# mppt.net
KiCad netlist of a schematic drawn in EAGLE
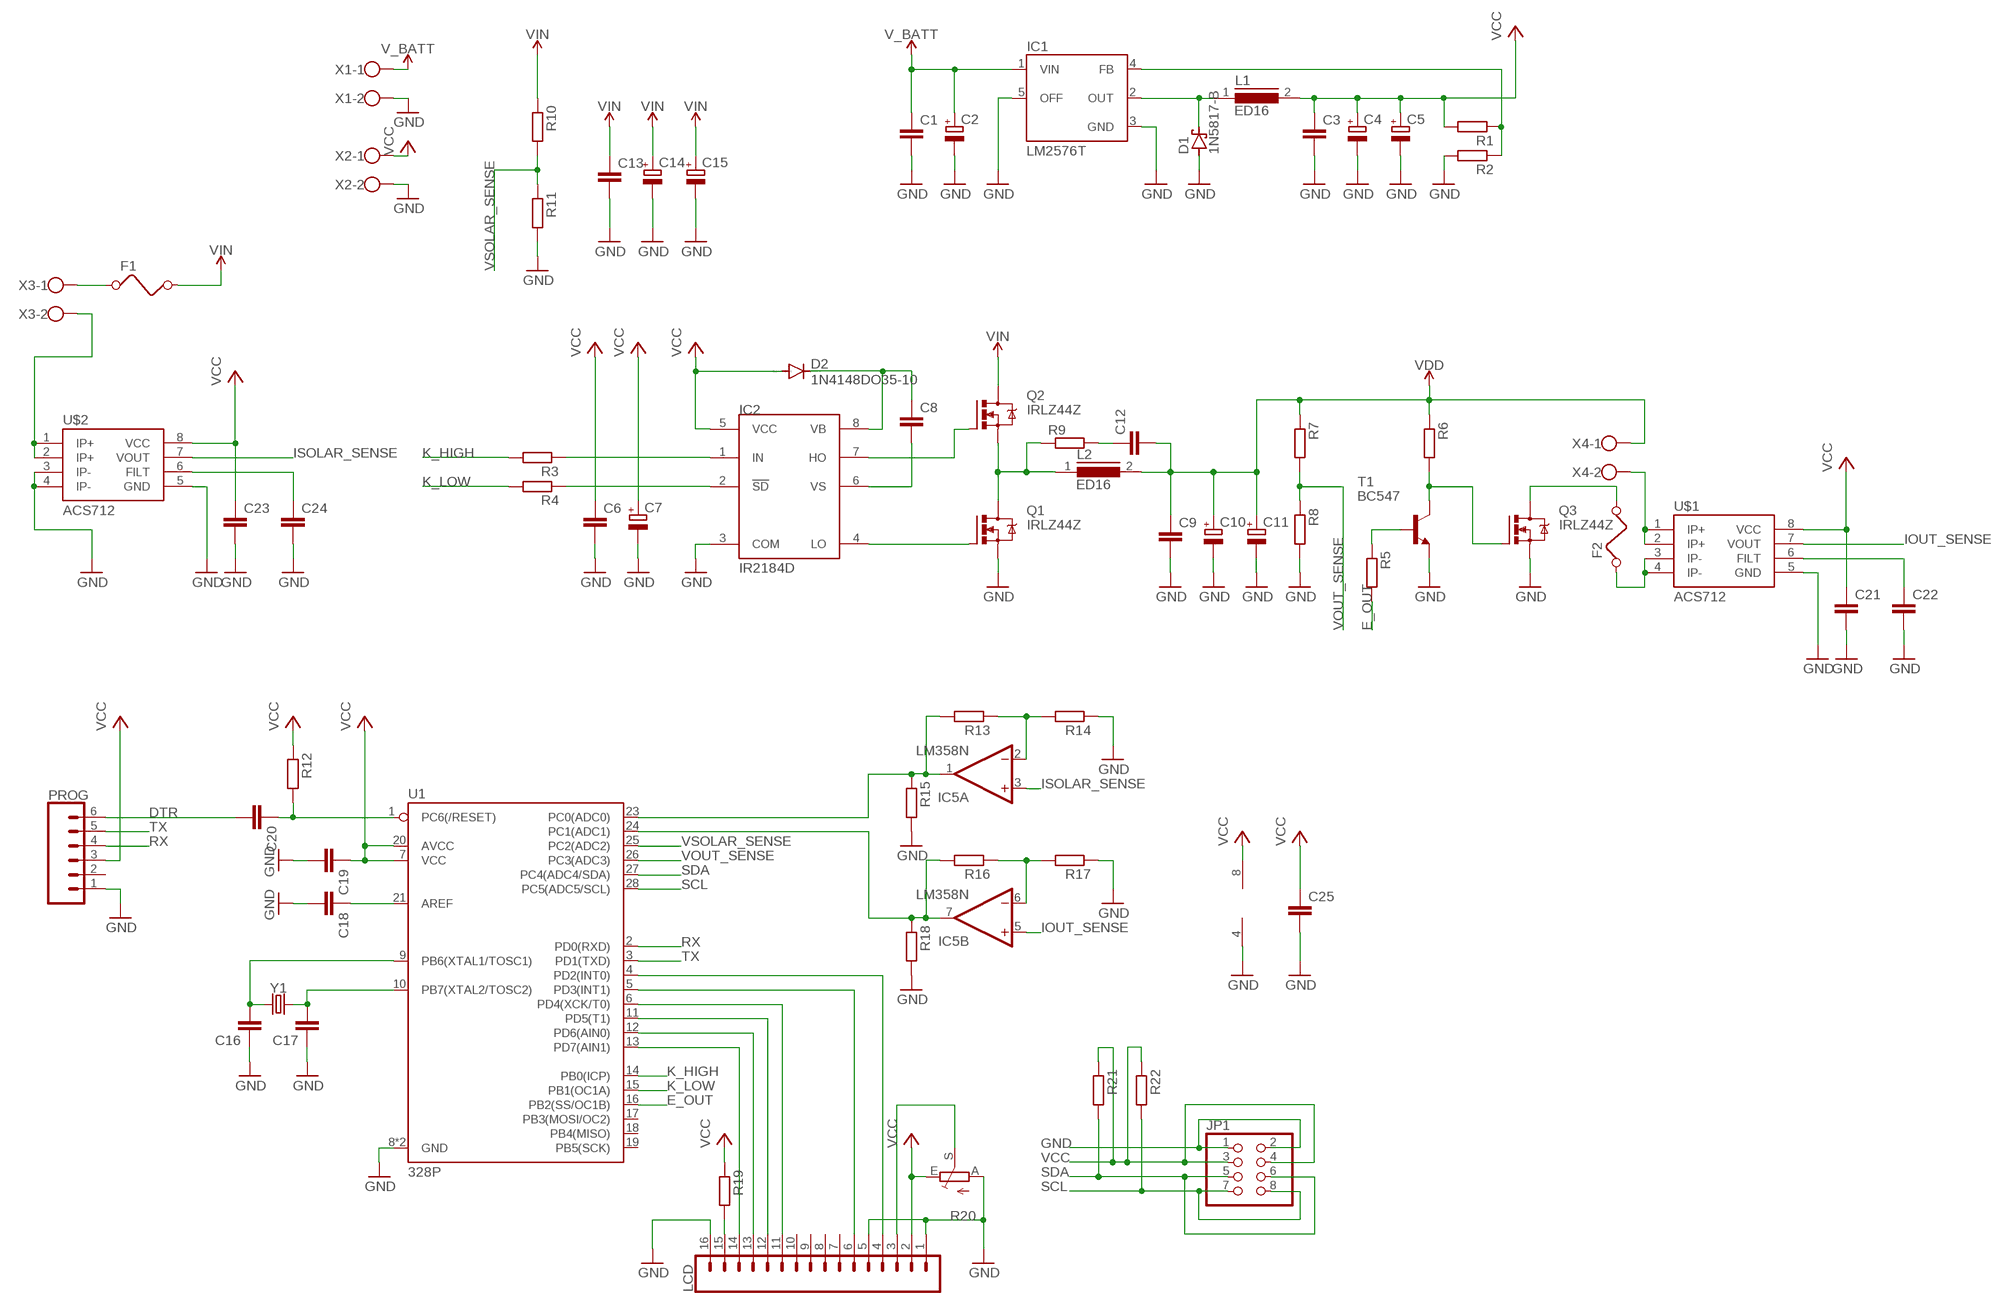
[diagram p0: schematic, sheet 1]

(export (version "E")
  (design (tool "Eeschema 10.0.6"))
  (components
    (comp (ref "C1")
      (value "C-EU025-024X044")
      (footprint "eagle-import:C025-024X044")
      (libsource (lib "eagle-import") (part "C-EU025-024X044"))
    )
    (comp (ref "C2")
      (value "CPOL-EUE5-6")
      (footprint "eagle-import:E5-6")
      (libsource (lib "eagle-import") (part "CPOL-EUE5-6"))
    )
    (comp (ref "C3")
      (value "C-EU025-024X044")
      (footprint "eagle-import:C025-024X044")
      (libsource (lib "eagle-import") (part "C-EU025-024X044"))
    )
    (comp (ref "C4")
      (value "CPOL-EUE5-6")
      (footprint "eagle-import:E5-6")
      (libsource (lib "eagle-import") (part "CPOL-EUE5-6"))
    )
    (comp (ref "C5")
      (value "CPOL-EUE5-6")
      (footprint "eagle-import:E5-6")
      (libsource (lib "eagle-import") (part "CPOL-EUE5-6"))
    )
    (comp (ref "C6")
      (value "C-EU025-024X044")
      (footprint "eagle-import:C025-024X044")
      (libsource (lib "eagle-import") (part "C-EU025-024X044"))
    )
    (comp (ref "C7")
      (value "CPOL-EUE5-6")
      (footprint "eagle-import:E5-6")
      (libsource (lib "eagle-import") (part "CPOL-EUE5-6"))
    )
    (comp (ref "C8")
      (value "C-EU025-024X044")
      (footprint "eagle-import:C025-024X044")
      (libsource (lib "eagle-import") (part "C-EU025-024X044"))
    )
    (comp (ref "C9")
      (value "C-EU025-024X044")
      (footprint "eagle-import:C025-024X044")
      (libsource (lib "eagle-import") (part "C-EU025-024X044"))
    )
    (comp (ref "C10")
      (value "CPOL-EUE7.5-16")
      (footprint "eagle-import:E7,5-16")
      (libsource (lib "eagle-import") (part "CPOL-EUE7.5-16"))
    )
    (comp (ref "C11")
      (value "CPOL-EUE7.5-16")
      (footprint "eagle-import:E7,5-16")
      (libsource (lib "eagle-import") (part "CPOL-EUE7.5-16"))
    )
    (comp (ref "C12")
      (value "C-EU025-024X044")
      (footprint "eagle-import:C025-024X044")
      (libsource (lib "eagle-import") (part "C-EU025-024X044"))
    )
    (comp (ref "C13")
      (value "C-EU025-024X044")
      (footprint "eagle-import:C025-024X044")
      (libsource (lib "eagle-import") (part "C-EU025-024X044"))
    )
    (comp (ref "C14")
      (value "CPOL-EUE7.5-16")
      (footprint "eagle-import:E7,5-16")
      (libsource (lib "eagle-import") (part "CPOL-EUE7.5-16"))
    )
    (comp (ref "C15")
      (value "CPOL-EUE7.5-16")
      (footprint "eagle-import:E7,5-16")
      (libsource (lib "eagle-import") (part "CPOL-EUE7.5-16"))
    )
    (comp (ref "C16")
      (value "C-EU025-024X044")
      (footprint "eagle-import:C025-024X044")
      (libsource (lib "eagle-import") (part "C-EU025-024X044"))
    )
    (comp (ref "C17")
      (value "C-EU025-024X044")
      (footprint "eagle-import:C025-024X044")
      (libsource (lib "eagle-import") (part "C-EU025-024X044"))
    )
    (comp (ref "C18")
      (value "C-EU025-024X044")
      (footprint "eagle-import:C025-024X044")
      (libsource (lib "eagle-import") (part "C-EU025-024X044"))
    )
    (comp (ref "C19")
      (value "C-EU025-024X044")
      (footprint "eagle-import:C025-024X044")
      (libsource (lib "eagle-import") (part "C-EU025-024X044"))
    )
    (comp (ref "C20")
      (value "C-EU025-024X044")
      (footprint "eagle-import:C025-024X044")
      (libsource (lib "eagle-import") (part "C-EU025-024X044"))
    )
    (comp (ref "C21")
      (value "C-EU025-024X044")
      (footprint "eagle-import:C025-024X044")
      (libsource (lib "eagle-import") (part "C-EU025-024X044"))
    )
    (comp (ref "C22")
      (value "C-EU025-024X044")
      (footprint "eagle-import:C025-024X044")
      (libsource (lib "eagle-import") (part "C-EU025-024X044"))
    )
    (comp (ref "C23")
      (value "C-EU025-024X044")
      (footprint "eagle-import:C025-024X044")
      (libsource (lib "eagle-import") (part "C-EU025-024X044"))
    )
    (comp (ref "C24")
      (value "C-EU025-024X044")
      (footprint "eagle-import:C025-024X044")
      (libsource (lib "eagle-import") (part "C-EU025-024X044"))
    )
    (comp (ref "C25")
      (value "C-EU025-024X044")
      (footprint "eagle-import:C025-024X044")
      (libsource (lib "eagle-import") (part "C-EU025-024X044"))
    )
    (comp (ref "D1")
      (value "1N5817-B")
      (footprint "eagle-import:DO41-7.6")
      (libsource (lib "eagle-import") (part "1N5817-B"))
    )
    (comp (ref "D2")
      (value "1N4148DO35-10")
      (footprint "eagle-import:DO35-10")
      (libsource (lib "eagle-import") (part "1N4148DO35-10"))
    )
    (comp (ref "F1")
      (value "FUSE")
      (footprint "eagle-import:FUSE")
      (libsource (lib "eagle-import") (part "FUSE"))
    )
    (comp (ref "F2")
      (value "FUSE")
      (footprint "eagle-import:FUSE")
      (libsource (lib "eagle-import") (part "FUSE"))
    )
    (comp (ref "IC1")
      (value "LM2576T")
      (footprint "eagle-import:TO220-5")
      (libsource (lib "eagle-import") (part "LM2576T"))
    )
    (comp (ref "IC2")
      (value "IR2184D")
      (footprint "eagle-import:DIL08")
      (libsource (lib "eagle-import") (part "IR2184D"))
    )
    (comp (ref "IC5")
      (value "LM358N")
      (footprint "eagle-import:DIL08")
      (libsource (lib "eagle-import") (part "LM358N"))
    )
    (comp (ref "JP1")
      (value "PINHD-2X4")
      (footprint "eagle-import:2X04")
      (libsource (lib "eagle-import") (part "PINHD-2X4"))
    )
    (comp (ref "L1")
      (value "ED16")
      (footprint "eagle-import:ED16")
      (libsource (lib "eagle-import") (part "ED16"))
    )
    (comp (ref "L2")
      (value "ED16")
      (footprint "eagle-import:ED16")
      (libsource (lib "eagle-import") (part "ED16"))
    )
    (comp (ref "LCD")
      (value "CONN_16LONGPADS")
      (footprint "eagle-import:1X16_LONGPADS")
      (libsource (lib "eagle-import") (part "CONN_16LONGPADS"))
    )
    (comp (ref "PROG")
      (value "CONN_06LONGPADS")
      (footprint "eagle-import:1X06_LONGPADS")
      (libsource (lib "eagle-import") (part "CONN_06LONGPADS"))
    )
    (comp (ref "Q1")
      (value "IRLZ44Z")
      (footprint "eagle-import:TO220BH")
      (libsource (lib "eagle-import") (part "IRLZ44Z"))
    )
    (comp (ref "Q2")
      (value "IRLZ44Z")
      (footprint "eagle-import:TO220BH")
      (libsource (lib "eagle-import") (part "IRLZ44Z"))
    )
    (comp (ref "Q3")
      (value "IRLZ44Z")
      (footprint "eagle-import:TO220BH")
      (libsource (lib "eagle-import") (part "IRLZ44Z"))
    )
    (comp (ref "R1")
      (value "R-EU_0207/10")
      (footprint "eagle-import:0207_10")
      (libsource (lib "eagle-import") (part "R-EU_0207/10"))
    )
    (comp (ref "R2")
      (value "R-EU_0207/10")
      (footprint "eagle-import:0207_10")
      (libsource (lib "eagle-import") (part "R-EU_0207/10"))
    )
    (comp (ref "R3")
      (value "R-EU_0207/10")
      (footprint "eagle-import:0207_10")
      (libsource (lib "eagle-import") (part "R-EU_0207/10"))
    )
    (comp (ref "R4")
      (value "R-EU_0207/10")
      (footprint "eagle-import:0207_10")
      (libsource (lib "eagle-import") (part "R-EU_0207/10"))
    )
    (comp (ref "R5")
      (value "R-EU_0207/10")
      (footprint "eagle-import:0207_10")
      (libsource (lib "eagle-import") (part "R-EU_0207/10"))
    )
    (comp (ref "R6")
      (value "R-EU_0207/10")
      (footprint "eagle-import:0207_10")
      (libsource (lib "eagle-import") (part "R-EU_0207/10"))
    )
    (comp (ref "R7")
      (value "R-EU_0207/10")
      (footprint "eagle-import:0207_10")
      (libsource (lib "eagle-import") (part "R-EU_0207/10"))
    )
    (comp (ref "R8")
      (value "R-EU_0207/10")
      (footprint "eagle-import:0207_10")
      (libsource (lib "eagle-import") (part "R-EU_0207/10"))
    )
    (comp (ref "R9")
      (value "R-EU_0207/10")
      (footprint "eagle-import:0207_10")
      (libsource (lib "eagle-import") (part "R-EU_0207/10"))
    )
    (comp (ref "R10")
      (value "R-EU_0207/10")
      (footprint "eagle-import:0207_10")
      (libsource (lib "eagle-import") (part "R-EU_0207/10"))
    )
    (comp (ref "R11")
      (value "R-EU_0207/10")
      (footprint "eagle-import:0207_10")
      (libsource (lib "eagle-import") (part "R-EU_0207/10"))
    )
    (comp (ref "R12")
      (value "R-EU_0207/10")
      (footprint "eagle-import:0207_10")
      (libsource (lib "eagle-import") (part "R-EU_0207/10"))
    )
    (comp (ref "R13")
      (value "R-EU_0207/10")
      (footprint "eagle-import:0207_10")
      (libsource (lib "eagle-import") (part "R-EU_0207/10"))
    )
    (comp (ref "R14")
      (value "R-EU_0207/10")
      (footprint "eagle-import:0207_10")
      (libsource (lib "eagle-import") (part "R-EU_0207/10"))
    )
    (comp (ref "R15")
      (value "R-EU_0207/10")
      (footprint "eagle-import:0207_10")
      (libsource (lib "eagle-import") (part "R-EU_0207/10"))
    )
    (comp (ref "R16")
      (value "R-EU_0207/10")
      (footprint "eagle-import:0207_10")
      (libsource (lib "eagle-import") (part "R-EU_0207/10"))
    )
    (comp (ref "R17")
      (value "R-EU_0207/10")
      (footprint "eagle-import:0207_10")
      (libsource (lib "eagle-import") (part "R-EU_0207/10"))
    )
    (comp (ref "R18")
      (value "R-EU_0207/10")
      (footprint "eagle-import:0207_10")
      (libsource (lib "eagle-import") (part "R-EU_0207/10"))
    )
    (comp (ref "R19")
      (value "R-EU_0207/10")
      (footprint "eagle-import:0207_10")
      (libsource (lib "eagle-import") (part "R-EU_0207/10"))
    )
    (comp (ref "R20")
      (value "TRIM_EU-B64Y")
      (footprint "eagle-import:B64Y")
      (libsource (lib "eagle-import") (part "TRIM_EU-B64Y"))
    )
    (comp (ref "R21")
      (value "R-EU_0207/10")
      (footprint "eagle-import:0207_10")
      (libsource (lib "eagle-import") (part "R-EU_0207/10"))
    )
    (comp (ref "R22")
      (value "R-EU_0207/10")
      (footprint "eagle-import:0207_10")
      (libsource (lib "eagle-import") (part "R-EU_0207/10"))
    )
    (comp (ref "T1")
      (value "BC547")
      (footprint "eagle-import:TO92")
      (libsource (lib "eagle-import") (part "BC547"))
    )
    (comp (ref "U$1")
      (value "ACS712")
      (footprint "eagle-import:SO08")
      (libsource (lib "eagle-import") (part "ACS712"))
    )
    (comp (ref "U$2")
      (value "ACS712")
      (footprint "eagle-import:SO08")
      (libsource (lib "eagle-import") (part "ACS712"))
    )
    (comp (ref "U1")
      (value "328P")
      (footprint "eagle-import:DIP28")
      (libsource (lib "eagle-import") (part "ATMEGA328P_PDIP"))
    )
    (comp (ref "X1")
      (value "W237-102")
      (footprint "eagle-import:W237-102")
      (fields (field (name "MPN") "237-102"))
      (libsource (lib "eagle-import") (part "W237-102"))
    )
    (comp (ref "X2")
      (value "W237-102")
      (footprint "eagle-import:W237-102")
      (fields (field (name "MPN") "237-102"))
      (libsource (lib "eagle-import") (part "W237-102"))
    )
    (comp (ref "X3")
      (value "W237-102")
      (footprint "eagle-import:W237-102")
      (fields (field (name "MPN") "237-102"))
      (libsource (lib "eagle-import") (part "W237-102"))
    )
    (comp (ref "X4")
      (value "W237-102")
      (footprint "eagle-import:W237-102")
      (fields (field (name "MPN") "237-102"))
      (libsource (lib "eagle-import") (part "W237-102"))
    )
    (comp (ref "Y1")
      (value "CRYSTALPTH-HC49UV")
      (footprint "eagle-import:HC49U")
      (libsource (lib "eagle-import") (part "CRYSTALPTH-HC49UV"))
    )
  )
  (nets
    (net (code "1") (name "/DTR") (class "Default")
      (node (ref "C20") (pin "2") (pinfunction "2_2") (pintype "passive"))
      (node (ref "PROG") (pin "6") (pinfunction "6_6") (pintype "passive"))
    )
    (net (code "2") (name "/E_OUT") (class "Default")
      (node (ref "R5") (pin "2") (pinfunction "2_2") (pintype "passive"))
      (node (ref "U1") (pin "16") (pinfunction "PB2(SS/OC1B)_16") (pintype "bidirectional"))
    )
    (net (code "3") (name "/IOUT_SENSE") (class "Default")
      (node (ref "IC5") (pin "5") (pinfunction "+IN_5") (pintype "input"))
      (node (ref "U$1") (pin "7") (pinfunction "VOUT_7") (pintype "bidirectional"))
    )
    (net (code "4") (name "/ISOLAR_SENSE") (class "Default")
      (node (ref "IC5") (pin "3") (pinfunction "+IN_3") (pintype "input"))
      (node (ref "U$2") (pin "7") (pinfunction "VOUT_7") (pintype "bidirectional"))
    )
    (net (code "5") (name "/K_HIGH") (class "Default")
      (node (ref "R3") (pin "2") (pinfunction "2_2") (pintype "passive"))
      (node (ref "U1") (pin "14") (pinfunction "PB0(ICP)_14") (pintype "bidirectional"))
    )
    (net (code "6") (name "/K_LOW") (class "Default")
      (node (ref "R4") (pin "2") (pinfunction "2_2") (pintype "passive"))
      (node (ref "U1") (pin "15") (pinfunction "PB1(OC1A)_15") (pintype "bidirectional"))
    )
    (net (code "7") (name "/RX") (class "Default")
      (node (ref "PROG") (pin "4") (pinfunction "4_4") (pintype "passive"))
      (node (ref "U1") (pin "2") (pinfunction "PD0(RXD)_2") (pintype "bidirectional"))
    )
    (net (code "8") (name "/SCL") (class "Default")
      (node (ref "JP1") (pin "7") (pinfunction "7_7") (pintype "passive"))
      (node (ref "JP1") (pin "8") (pinfunction "8_8") (pintype "passive"))
      (node (ref "R22") (pin "2") (pinfunction "2_2") (pintype "passive"))
      (node (ref "U1") (pin "28") (pinfunction "PC5(ADC5/SCL)_28") (pintype "bidirectional"))
    )
    (net (code "9") (name "/SDA") (class "Default")
      (node (ref "JP1") (pin "5") (pinfunction "5_5") (pintype "passive"))
      (node (ref "JP1") (pin "6") (pinfunction "6_6") (pintype "passive"))
      (node (ref "R21") (pin "2") (pinfunction "2_2") (pintype "passive"))
      (node (ref "U1") (pin "27") (pinfunction "PC4(ADC4/SDA)_27") (pintype "bidirectional"))
    )
    (net (code "10") (name "/TX") (class "Default")
      (node (ref "PROG") (pin "5") (pinfunction "5_5") (pintype "passive"))
      (node (ref "U1") (pin "3") (pinfunction "PD1(TXD)_3") (pintype "bidirectional"))
    )
    (net (code "11") (name "/VOUT_SENSE") (class "Default")
      (node (ref "R7") (pin "2") (pinfunction "2_2") (pintype "passive"))
      (node (ref "R8") (pin "1") (pinfunction "1_1") (pintype "passive"))
      (node (ref "U1") (pin "26") (pinfunction "PC3(ADC3)_26") (pintype "bidirectional"))
    )
    (net (code "12") (name "/VSOLAR_SENSE") (class "Default")
      (node (ref "R10") (pin "2") (pinfunction "2_2") (pintype "passive"))
      (node (ref "R11") (pin "1") (pinfunction "1_1") (pintype "passive"))
      (node (ref "U1") (pin "25") (pinfunction "PC2(ADC2)_25") (pintype "bidirectional"))
    )
    (net (code "13") (name "GND") (class "Default")
      (node (ref "C1") (pin "2") (pinfunction "2_2") (pintype "passive"))
      (node (ref "C10") (pin "-") (pinfunction "-_-") (pintype "passive"))
      (node (ref "C11") (pin "-") (pinfunction "-_-") (pintype "passive"))
      (node (ref "C13") (pin "2") (pinfunction "2_2") (pintype "passive"))
      (node (ref "C14") (pin "-") (pinfunction "-_-") (pintype "passive"))
      (node (ref "C15") (pin "-") (pinfunction "-_-") (pintype "passive"))
      (node (ref "C16") (pin "1") (pinfunction "1_1") (pintype "passive"))
      (node (ref "C17") (pin "1") (pinfunction "1_1") (pintype "passive"))
      (node (ref "C18") (pin "2") (pinfunction "2_2") (pintype "passive"))
      (node (ref "C19") (pin "2") (pinfunction "2_2") (pintype "passive"))
      (node (ref "C2") (pin "-") (pinfunction "-_-") (pintype "passive"))
      (node (ref "C21") (pin "2") (pinfunction "2_2") (pintype "passive"))
      (node (ref "C22") (pin "2") (pinfunction "2_2") (pintype "passive"))
      (node (ref "C23") (pin "2") (pinfunction "2_2") (pintype "passive"))
      (node (ref "C24") (pin "2") (pinfunction "2_2") (pintype "passive"))
      (node (ref "C25") (pin "2") (pinfunction "2_2") (pintype "passive"))
      (node (ref "C3") (pin "2") (pinfunction "2_2") (pintype "passive"))
      (node (ref "C4") (pin "-") (pinfunction "-_-") (pintype "passive"))
      (node (ref "C5") (pin "-") (pinfunction "-_-") (pintype "passive"))
      (node (ref "C6") (pin "2") (pinfunction "2_2") (pintype "passive"))
      (node (ref "C7") (pin "-") (pinfunction "-_-") (pintype "passive"))
      (node (ref "C9") (pin "2") (pinfunction "2_2") (pintype "passive"))
      (node (ref "D1") (pin "A") (pinfunction "A_A") (pintype "passive"))
      (node (ref "IC1") (pin "3") (pinfunction "GND_3") (pintype "power_in"))
      (node (ref "IC1") (pin "5") (pinfunction "OFF_5") (pintype "input"))
      (node (ref "IC2") (pin "3") (pinfunction "COM_3") (pintype "power_in"))
      (node (ref "IC5") (pin "4") (pinfunction "V-_4") (pintype "power_in"))
      (node (ref "JP1") (pin "1") (pinfunction "1_1") (pintype "passive"))
      (node (ref "JP1") (pin "2") (pinfunction "2_2") (pintype "passive"))
      (node (ref "LCD") (pin "1") (pinfunction "1_1") (pintype "passive"))
      (node (ref "LCD") (pin "16") (pinfunction "16_16") (pintype "passive"))
      (node (ref "LCD") (pin "5") (pinfunction "5_5") (pintype "passive"))
      (node (ref "PROG") (pin "1") (pinfunction "1_1") (pintype "passive"))
      (node (ref "Q1") (pin "S") (pinfunction "S_S") (pintype "passive"))
      (node (ref "Q3") (pin "S") (pinfunction "S_S") (pintype "passive"))
      (node (ref "R11") (pin "2") (pinfunction "2_2") (pintype "passive"))
      (node (ref "R14") (pin "1") (pinfunction "1_1") (pintype "passive"))
      (node (ref "R15") (pin "2") (pinfunction "2_2") (pintype "passive"))
      (node (ref "R17") (pin "1") (pinfunction "1_1") (pintype "passive"))
      (node (ref "R18") (pin "2") (pinfunction "2_2") (pintype "passive"))
      (node (ref "R2") (pin "2") (pinfunction "2_2") (pintype "passive"))
      (node (ref "R20") (pin "A") (pinfunction "A_A") (pintype "passive"))
      (node (ref "R8") (pin "2") (pinfunction "2_2") (pintype "passive"))
      (node (ref "T1") (pin "1") (pinfunction "E_1") (pintype "passive"))
      (node (ref "U$1") (pin "5") (pinfunction "GND_5") (pintype "bidirectional"))
      (node (ref "U$2") (pin "3") (pinfunction "IP-_3") (pintype "bidirectional"))
      (node (ref "U$2") (pin "4") (pinfunction "IP-_4") (pintype "bidirectional"))
      (node (ref "U$2") (pin "5") (pinfunction "GND_5") (pintype "bidirectional"))
      (node (ref "U1") (pin "22") (pinfunction "GND_22") (pintype "bidirectional"))
      (node (ref "U1") (pin "8") (pinfunction "GND_8") (pintype "bidirectional"))
      (node (ref "X1") (pin "2") (pinfunction "KL_2") (pintype "passive"))
      (node (ref "X2") (pin "2") (pinfunction "KL_2") (pintype "passive"))
    )
    (net (code "14") (name "Net-(C12-Pad1)") (class "Default")
      (node (ref "C12") (pin "1") (pinfunction "1_1") (pintype "passive"))
      (node (ref "R9") (pin "2") (pinfunction "2_2") (pintype "passive"))
    )
    (net (code "15") (name "Net-(F2-Pad1)") (class "Default")
      (node (ref "F2") (pin "1") (pinfunction "1_1") (pintype "passive"))
      (node (ref "U$1") (pin "3") (pinfunction "IP-_3") (pintype "bidirectional"))
      (node (ref "U$1") (pin "4") (pinfunction "IP-_4") (pintype "bidirectional"))
    )
    (net (code "16") (name "Net-(F2-Pad2)") (class "Default")
      (node (ref "F2") (pin "2") (pinfunction "2_2") (pintype "passive"))
      (node (ref "Q3") (pin "D") (pinfunction "D_D") (pintype "passive"))
    )
    (net (code "17") (name "Net-(IC1-FB)") (class "Default")
      (node (ref "IC1") (pin "4") (pinfunction "FB_4") (pintype "input"))
      (node (ref "R1") (pin "1") (pinfunction "1_1") (pintype "passive"))
      (node (ref "R2") (pin "1") (pinfunction "1_1") (pintype "passive"))
    )
    (net (code "18") (name "Net-(IC1-OUT)") (class "Default")
      (node (ref "D1") (pin "C") (pinfunction "C_C") (pintype "passive"))
      (node (ref "IC1") (pin "2") (pinfunction "OUT_2") (pintype "output"))
      (node (ref "L1") (pin "1") (pinfunction "1_1") (pintype "passive"))
    )
    (net (code "19") (name "Net-(IC2-HO)") (class "Default")
      (node (ref "IC2") (pin "7") (pinfunction "HO_7") (pintype "output"))
      (node (ref "Q2") (pin "G") (pinfunction "G_G") (pintype "passive"))
    )
    (net (code "20") (name "Net-(IC2-IN)") (class "Default")
      (node (ref "IC2") (pin "1") (pinfunction "IN_1") (pintype "input"))
      (node (ref "R3") (pin "1") (pinfunction "1_1") (pintype "passive"))
    )
    (net (code "21") (name "Net-(IC2-LO)") (class "Default")
      (node (ref "IC2") (pin "4") (pinfunction "LO_4") (pintype "output"))
      (node (ref "Q1") (pin "G") (pinfunction "G_G") (pintype "passive"))
    )
    (net (code "22") (name "Net-(IC2-VB)") (class "Default")
      (node (ref "C8") (pin "1") (pinfunction "1_1") (pintype "passive"))
      (node (ref "D2") (pin "C") (pinfunction "C_C") (pintype "passive"))
      (node (ref "IC2") (pin "8") (pinfunction "VB_8") (pintype "power_in"))
    )
    (net (code "23") (name "Net-(IC2-VS)") (class "Default")
      (node (ref "C8") (pin "2") (pinfunction "2_2") (pintype "passive"))
      (node (ref "IC2") (pin "6") (pinfunction "VS_6") (pintype "power_in"))
    )
    (net (code "24") (name "Net-(IC2-~{SD})") (class "Default")
      (node (ref "IC2") (pin "2") (pinfunction "~{SD}_2") (pintype "input"))
      (node (ref "R4") (pin "1") (pinfunction "1_1") (pintype "passive"))
    )
    (net (code "25") (name "Net-(IC5A--IN)") (class "Default")
      (node (ref "IC5") (pin "2") (pinfunction "-IN_2") (pintype "input"))
      (node (ref "R13") (pin "1") (pinfunction "1_1") (pintype "passive"))
      (node (ref "R14") (pin "2") (pinfunction "2_2") (pintype "passive"))
    )
    (net (code "26") (name "Net-(IC5A-OUT)") (class "Default")
      (node (ref "IC5") (pin "1") (pinfunction "OUT_1") (pintype "output"))
      (node (ref "R13") (pin "2") (pinfunction "2_2") (pintype "passive"))
      (node (ref "R15") (pin "1") (pinfunction "1_1") (pintype "passive"))
      (node (ref "U1") (pin "23") (pinfunction "PC0(ADC0)_23") (pintype "bidirectional"))
    )
    (net (code "27") (name "Net-(IC5B--IN)") (class "Default")
      (node (ref "IC5") (pin "6") (pinfunction "-IN_6") (pintype "input"))
      (node (ref "R16") (pin "1") (pinfunction "1_1") (pintype "passive"))
      (node (ref "R17") (pin "2") (pinfunction "2_2") (pintype "passive"))
    )
    (net (code "28") (name "Net-(IC5B-OUT)") (class "Default")
      (node (ref "IC5") (pin "7") (pinfunction "OUT_7") (pintype "output"))
      (node (ref "R16") (pin "2") (pinfunction "2_2") (pintype "passive"))
      (node (ref "R18") (pin "1") (pinfunction "1_1") (pintype "passive"))
      (node (ref "U1") (pin "24") (pinfunction "PC1(ADC1)_24") (pintype "bidirectional"))
    )
    (net (code "29") (name "Net-(L2-Pad1)") (class "Default")
      (node (ref "L2") (pin "1") (pinfunction "1_1") (pintype "passive"))
      (node (ref "Q1") (pin "D") (pinfunction "D_D") (pintype "passive"))
      (node (ref "Q2") (pin "S") (pinfunction "S_S") (pintype "passive"))
      (node (ref "R9") (pin "1") (pinfunction "1_1") (pintype "passive"))
    )
    (net (code "30") (name "Net-(LCD-Pad3)") (class "Default")
      (node (ref "LCD") (pin "3") (pinfunction "3_3") (pintype "passive"))
      (node (ref "R20") (pin "S") (pinfunction "S_S") (pintype "passive"))
    )
    (net (code "31") (name "Net-(LCD-Pad15)") (class "Default")
      (node (ref "LCD") (pin "15") (pinfunction "15_15") (pintype "passive"))
      (node (ref "R19") (pin "2") (pinfunction "2_2") (pintype "passive"))
    )
    (net (code "32") (name "Net-(T1-B)") (class "Default")
      (node (ref "R5") (pin "1") (pinfunction "1_1") (pintype "passive"))
      (node (ref "T1") (pin "2") (pinfunction "B_2") (pintype "passive"))
    )
    (net (code "33") (name "Net-(T1-C)") (class "Default")
      (node (ref "Q3") (pin "G") (pinfunction "G_G") (pintype "passive"))
      (node (ref "R6") (pin "2") (pinfunction "2_2") (pintype "passive"))
      (node (ref "T1") (pin "3") (pinfunction "C_3") (pintype "passive"))
    )
    (net (code "34") (name "Net-(U$1-FILT)") (class "Default")
      (node (ref "C22") (pin "1") (pinfunction "1_1") (pintype "passive"))
      (node (ref "U$1") (pin "6") (pinfunction "FILT_6") (pintype "bidirectional"))
    )
    (net (code "35") (name "Net-(U$2-FILT)") (class "Default")
      (node (ref "C24") (pin "1") (pinfunction "1_1") (pintype "passive"))
      (node (ref "U$2") (pin "6") (pinfunction "FILT_6") (pintype "bidirectional"))
    )
    (net (code "36") (name "Net-(U1-AREF)") (class "Default")
      (node (ref "C18") (pin "1") (pinfunction "1_1") (pintype "passive"))
      (node (ref "U1") (pin "21") (pinfunction "AREF_21") (pintype "bidirectional"))
    )
    (net (code "37") (name "Net-(U1-PB6(XTAL1{slash}TOSC1))") (class "Default")
      (node (ref "C16") (pin "2") (pinfunction "2_2") (pintype "passive"))
      (node (ref "U1") (pin "9") (pinfunction "PB6(XTAL1/TOSC1)_9") (pintype "bidirectional"))
      (node (ref "Y1") (pin "1") (pinfunction "1_1") (pintype "passive"))
    )
    (net (code "38") (name "Net-(U1-PB7(XTAL2{slash}TOSC2))") (class "Default")
      (node (ref "C17") (pin "2") (pinfunction "2_2") (pintype "passive"))
      (node (ref "U1") (pin "10") (pinfunction "PB7(XTAL2/TOSC2)_10") (pintype "bidirectional"))
      (node (ref "Y1") (pin "2") (pinfunction "2_2") (pintype "passive"))
    )
    (net (code "39") (name "Net-(U1-PC6({slash}RESET))") (class "Default")
      (node (ref "C20") (pin "1") (pinfunction "1_1") (pintype "passive"))
      (node (ref "R12") (pin "2") (pinfunction "2_2") (pintype "passive"))
      (node (ref "U1") (pin "1") (pinfunction "PC6(/RESET)_1") (pintype "bidirectional"))
    )
    (net (code "40") (name "Net-(U1-PD2(INT0))") (class "Default")
      (node (ref "LCD") (pin "4") (pinfunction "4_4") (pintype "passive"))
      (node (ref "U1") (pin "4") (pinfunction "PD2(INT0)_4") (pintype "bidirectional"))
    )
    (net (code "41") (name "Net-(U1-PD3(INT1))") (class "Default")
      (node (ref "LCD") (pin "6") (pinfunction "6_6") (pintype "passive"))
      (node (ref "U1") (pin "5") (pinfunction "PD3(INT1)_5") (pintype "bidirectional"))
    )
    (net (code "42") (name "Net-(U1-PD4(XCK{slash}T0))") (class "Default")
      (node (ref "LCD") (pin "11") (pinfunction "11_11") (pintype "passive"))
      (node (ref "U1") (pin "6") (pinfunction "PD4(XCK/T0)_6") (pintype "bidirectional"))
    )
    (net (code "43") (name "Net-(U1-PD5(T1))") (class "Default")
      (node (ref "LCD") (pin "12") (pinfunction "12_12") (pintype "passive"))
      (node (ref "U1") (pin "11") (pinfunction "PD5(T1)_11") (pintype "bidirectional"))
    )
    (net (code "44") (name "Net-(U1-PD6(AIN0))") (class "Default")
      (node (ref "LCD") (pin "13") (pinfunction "13_13") (pintype "passive"))
      (node (ref "U1") (pin "12") (pinfunction "PD6(AIN0)_12") (pintype "bidirectional"))
    )
    (net (code "45") (name "Net-(U1-PD7(AIN1))") (class "Default")
      (node (ref "LCD") (pin "14") (pinfunction "14_14") (pintype "passive"))
      (node (ref "U1") (pin "13") (pinfunction "PD7(AIN1)_13") (pintype "bidirectional"))
    )
    (net (code "46") (name "Net-(X3A-KL)") (class "Default")
      (node (ref "F1") (pin "1") (pinfunction "1_1") (pintype "passive"))
      (node (ref "X3") (pin "1") (pinfunction "KL_1") (pintype "passive"))
    )
    (net (code "47") (name "Net-(X3B-KL)") (class "Default")
      (node (ref "U$2") (pin "1") (pinfunction "IP+_1") (pintype "bidirectional"))
      (node (ref "U$2") (pin "2") (pinfunction "IP+_2") (pintype "bidirectional"))
      (node (ref "X3") (pin "2") (pinfunction "KL_2") (pintype "passive"))
    )
    (net (code "48") (name "Net-(X4B-KL)") (class "Default")
      (node (ref "U$1") (pin "1") (pinfunction "IP+_1") (pintype "bidirectional"))
      (node (ref "U$1") (pin "2") (pinfunction "IP+_2") (pintype "bidirectional"))
      (node (ref "X4") (pin "2") (pinfunction "KL_2") (pintype "passive"))
    )
    (net (code "49") (name "VCC") (class "Default")
      (node (ref "C19") (pin "1") (pinfunction "1_1") (pintype "passive"))
      (node (ref "C21") (pin "1") (pinfunction "1_1") (pintype "passive"))
      (node (ref "C23") (pin "1") (pinfunction "1_1") (pintype "passive"))
      (node (ref "C25") (pin "1") (pinfunction "1_1") (pintype "passive"))
      (node (ref "C3") (pin "1") (pinfunction "1_1") (pintype "passive"))
      (node (ref "C4") (pin "+") (pinfunction "+_+") (pintype "passive"))
      (node (ref "C5") (pin "+") (pinfunction "+_+") (pintype "passive"))
      (node (ref "C6") (pin "1") (pinfunction "1_1") (pintype "passive"))
      (node (ref "C7") (pin "+") (pinfunction "+_+") (pintype "passive"))
      (node (ref "D2") (pin "A") (pinfunction "A_A") (pintype "passive"))
      (node (ref "IC2") (pin "5") (pinfunction "VCC_5") (pintype "power_in"))
      (node (ref "IC5") (pin "8") (pinfunction "V+_8") (pintype "power_in"))
      (node (ref "JP1") (pin "3") (pinfunction "3_3") (pintype "passive"))
      (node (ref "JP1") (pin "4") (pinfunction "4_4") (pintype "passive"))
      (node (ref "L1") (pin "2") (pinfunction "2_2") (pintype "passive"))
      (node (ref "LCD") (pin "2") (pinfunction "2_2") (pintype "passive"))
      (node (ref "PROG") (pin "3") (pinfunction "3_3") (pintype "passive"))
      (node (ref "R1") (pin "2") (pinfunction "2_2") (pintype "passive"))
      (node (ref "R12") (pin "1") (pinfunction "1_1") (pintype "passive"))
      (node (ref "R19") (pin "1") (pinfunction "1_1") (pintype "passive"))
      (node (ref "R20") (pin "E") (pinfunction "E_E") (pintype "passive"))
      (node (ref "R21") (pin "1") (pinfunction "1_1") (pintype "passive"))
      (node (ref "R22") (pin "1") (pinfunction "1_1") (pintype "passive"))
      (node (ref "U$1") (pin "8") (pinfunction "VCC_8") (pintype "bidirectional"))
      (node (ref "U$2") (pin "8") (pinfunction "VCC_8") (pintype "bidirectional"))
      (node (ref "U1") (pin "20") (pinfunction "AVCC_20") (pintype "bidirectional"))
      (node (ref "U1") (pin "7") (pinfunction "VCC_7") (pintype "bidirectional"))
      (node (ref "X2") (pin "1") (pinfunction "KL_1") (pintype "passive"))
    )
    (net (code "50") (name "VDD") (class "Default")
      (node (ref "C10") (pin "+") (pinfunction "+_+") (pintype "passive"))
      (node (ref "C11") (pin "+") (pinfunction "+_+") (pintype "passive"))
      (node (ref "C12") (pin "2") (pinfunction "2_2") (pintype "passive"))
      (node (ref "C9") (pin "1") (pinfunction "1_1") (pintype "passive"))
      (node (ref "L2") (pin "2") (pinfunction "2_2") (pintype "passive"))
      (node (ref "R6") (pin "1") (pinfunction "1_1") (pintype "passive"))
      (node (ref "R7") (pin "1") (pinfunction "1_1") (pintype "passive"))
      (node (ref "X4") (pin "1") (pinfunction "KL_1") (pintype "passive"))
    )
    (net (code "51") (name "VIN") (class "Default")
      (node (ref "C13") (pin "1") (pinfunction "1_1") (pintype "passive"))
      (node (ref "C14") (pin "+") (pinfunction "+_+") (pintype "passive"))
      (node (ref "C15") (pin "+") (pinfunction "+_+") (pintype "passive"))
      (node (ref "F1") (pin "2") (pinfunction "2_2") (pintype "passive"))
      (node (ref "Q2") (pin "D") (pinfunction "D_D") (pintype "passive"))
      (node (ref "R10") (pin "1") (pinfunction "1_1") (pintype "passive"))
    )
    (net (code "52") (name "V_BATT") (class "Default")
      (node (ref "C1") (pin "1") (pinfunction "1_1") (pintype "passive"))
      (node (ref "C2") (pin "+") (pinfunction "+_+") (pintype "passive"))
      (node (ref "IC1") (pin "1") (pinfunction "VIN_1") (pintype "power_in"))
      (node (ref "X1") (pin "1") (pinfunction "KL_1") (pintype "passive"))
    )
    (net (code "53") (name "unconnected-(LCD-Pad7)") (class "Default")
      (node (ref "LCD") (pin "7") (pinfunction "7_7") (pintype "passive"))
    )
    (net (code "54") (name "unconnected-(LCD-Pad8)") (class "Default")
      (node (ref "LCD") (pin "8") (pinfunction "8_8") (pintype "passive"))
    )
    (net (code "55") (name "unconnected-(LCD-Pad9)") (class "Default")
      (node (ref "LCD") (pin "9") (pinfunction "9_9") (pintype "passive"))
    )
    (net (code "56") (name "unconnected-(LCD-Pad10)") (class "Default")
      (node (ref "LCD") (pin "10") (pinfunction "10_10") (pintype "passive"))
    )
    (net (code "57") (name "unconnected-(PROG-Pad2)") (class "Default")
      (node (ref "PROG") (pin "2") (pinfunction "2_2") (pintype "passive"))
    )
    (net (code "58") (name "unconnected-(U1-PB3(MOSI{slash}OC2)-Pad17)") (class "Default")
      (node (ref "U1") (pin "17") (pinfunction "PB3(MOSI/OC2)_17") (pintype "bidirectional"))
    )
    (net (code "59") (name "unconnected-(U1-PB4(MISO)-Pad18)") (class "Default")
      (node (ref "U1") (pin "18") (pinfunction "PB4(MISO)_18") (pintype "bidirectional"))
    )
    (net (code "60") (name "unconnected-(U1-PB5(SCK)-Pad19)") (class "Default")
      (node (ref "U1") (pin "19") (pinfunction "PB5(SCK)_19") (pintype "bidirectional"))
    )
  )
)
